# karmanDB_MCU.net
KiCad netlist of a schematic drawn in Altium Designer
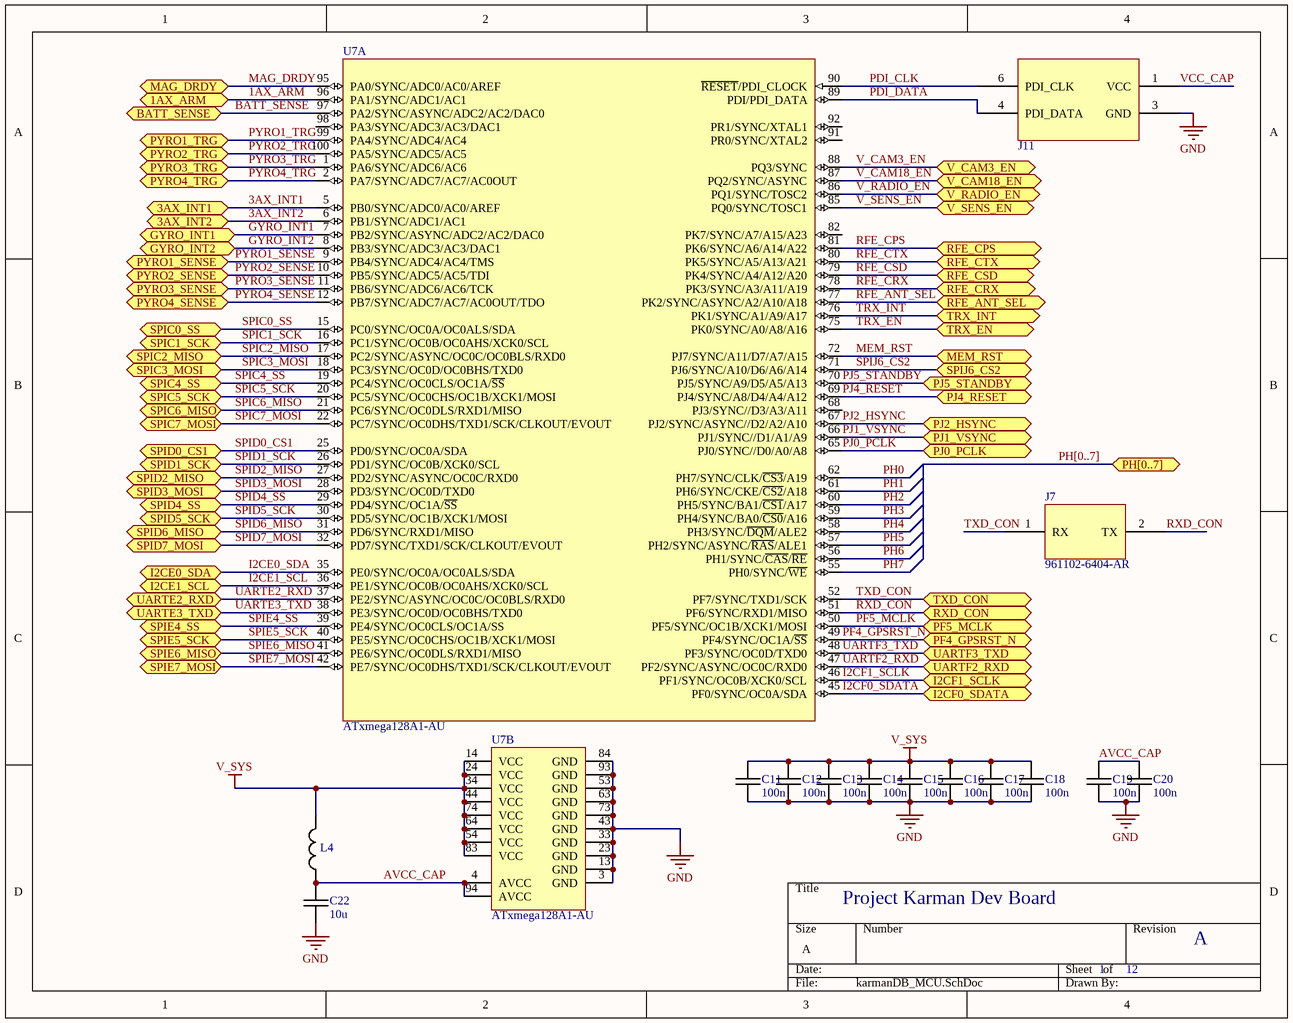
[diagram p0: karmanDB_MCU.SchDoc]

(export (version "E")
  (design (tool "Eeschema 10.0.6"))
  (components
    (comp (ref "C11")
      (value "100n")
      (footprint "MURATA_GRM_0603")
      (description "CAP CER 0.1UF 6.3V 10% X7R 0603")
      (fields
        (field (name "MANUFACTURER") "Murata Electronics North America")
        (field (name "MANUFACTURER PART NUMBER") "GRM188R70J104KA01D")
      )
      (libsource (lib "project_symbols") (part "CAP_MURATA_GRM188R70J104KA01D"))
    )
    (comp (ref "C12")
      (value "100n")
      (footprint "MURATA_GRM_0603")
      (description "CAP CER 0.1UF 6.3V 10% X7R 0603")
      (fields
        (field (name "MANUFACTURER") "Murata Electronics North America")
        (field (name "MANUFACTURER PART NUMBER") "GRM188R70J104KA01D")
      )
      (libsource (lib "project_symbols") (part "CAP_MURATA_GRM188R70J104KA01D"))
    )
    (comp (ref "C13")
      (value "100n")
      (footprint "MURATA_GRM_0603")
      (description "CAP CER 0.1UF 6.3V 10% X7R 0603")
      (fields
        (field (name "MANUFACTURER") "Murata Electronics North America")
        (field (name "MANUFACTURER PART NUMBER") "GRM188R70J104KA01D")
      )
      (libsource (lib "project_symbols") (part "CAP_MURATA_GRM188R70J104KA01D"))
    )
    (comp (ref "C14")
      (value "100n")
      (footprint "MURATA_GRM_0603")
      (description "CAP CER 0.1UF 6.3V 10% X7R 0603")
      (fields
        (field (name "MANUFACTURER") "Murata Electronics North America")
        (field (name "MANUFACTURER PART NUMBER") "GRM188R70J104KA01D")
      )
      (libsource (lib "project_symbols") (part "CAP_MURATA_GRM188R70J104KA01D"))
    )
    (comp (ref "C15")
      (value "100n")
      (footprint "MURATA_GRM_0603")
      (description "CAP CER 0.1UF 6.3V 10% X7R 0603")
      (fields
        (field (name "MANUFACTURER") "Murata Electronics North America")
        (field (name "MANUFACTURER PART NUMBER") "GRM188R70J104KA01D")
      )
      (libsource (lib "project_symbols") (part "CAP_MURATA_GRM188R70J104KA01D"))
    )
    (comp (ref "C16")
      (value "100n")
      (footprint "MURATA_GRM_0603")
      (description "CAP CER 0.1UF 6.3V 10% X7R 0603")
      (fields
        (field (name "MANUFACTURER") "Murata Electronics North America")
        (field (name "MANUFACTURER PART NUMBER") "GRM188R70J104KA01D")
      )
      (libsource (lib "project_symbols") (part "CAP_MURATA_GRM188R70J104KA01D"))
    )
    (comp (ref "C17")
      (value "100n")
      (footprint "MURATA_GRM_0603")
      (description "CAP CER 0.1UF 6.3V 10% X7R 0603")
      (fields
        (field (name "MANUFACTURER") "Murata Electronics North America")
        (field (name "MANUFACTURER PART NUMBER") "GRM188R70J104KA01D")
      )
      (libsource (lib "project_symbols") (part "CAP_MURATA_GRM188R70J104KA01D"))
    )
    (comp (ref "C18")
      (value "100n")
      (footprint "MURATA_GRM_0603")
      (description "CAP CER 0.1UF 6.3V 10% X7R 0603")
      (fields
        (field (name "MANUFACTURER") "Murata Electronics North America")
        (field (name "MANUFACTURER PART NUMBER") "GRM188R70J104KA01D")
      )
      (libsource (lib "project_symbols") (part "CAP_MURATA_GRM188R70J104KA01D"))
    )
    (comp (ref "C19")
      (value "100n")
      (footprint "MURATA_GRM_0603")
      (description "CAP CER 0.1UF 6.3V 10% X7R 0603")
      (fields
        (field (name "MANUFACTURER") "Murata Electronics North America")
        (field (name "MANUFACTURER PART NUMBER") "GRM188R70J104KA01D")
      )
      (libsource (lib "project_symbols") (part "CAP_MURATA_GRM188R70J104KA01D"))
    )
    (comp (ref "C20")
      (value "100n")
      (footprint "MURATA_GRM_0603")
      (description "CAP CER 0.1UF 6.3V 10% X7R 0603")
      (fields
        (field (name "MANUFACTURER") "Murata Electronics North America")
        (field (name "MANUFACTURER PART NUMBER") "GRM188R70J104KA01D")
      )
      (libsource (lib "project_symbols") (part "CAP_MURATA_GRM188R70J104KA01D"))
    )
    (comp (ref "C22")
      (value "10u")
      (footprint "MURATA_GRM_0603")
      (description "CAP CER 10UF 6.3V 20% X5R 0603")
      (fields
        (field (name "MANUFACTURER") "Murata Electronics North America")
        (field (name "MANUFACTURER PART NUMBER") "GRM188R60J106ME47J")
      )
      (libsource (lib "project_symbols") (part "CAP_MURATA_GRM188R60J106"))
    )
    (comp (ref "J7")
      (value "961102-6404-AR")
      (footprint "3M_961102-6X04")
      (description "CONN HEADER VERT SGL 2POS GOLD")
      (fields (field (name "MANUFACTURER") "3M"))
      (libsource (lib "karman_pcb") (part "961102-6404-AR"))
    )
    (comp (ref "J11")
      (value "961206-6404-AR")
      (footprint "961206-6404-AR")
      (description "CONN HEADER VERT DUAL 6POS GOLD")
      (fields (field (name "MANUFACTURER") "3M"))
      (libsource (lib "karman_pcb") (part "961206-6404-AR"))
    )
    (comp (ref "L4")
      (value "BLM15BB221SN1D")
      (footprint "BLM15")
      (description "FERRITE CHIP 220 OHM 200MA 0402")
      (fields (field (name "MANUFACTURER") "Murata Electronics North America"))
      (libsource (lib "karman_pcb") (part "BLM15BB221SN1D"))
    )
    (comp (ref "U7")
      (value "ATxmega128A1-AU")
      (footprint "100A_N")
      (fields (field (name "PUBLISHER") "Altium Limited"))
      (libsource (lib "Atmel Microcontroller 8-16-Bit AVR XMEGA") (part "ATxmega128A1-AU"))
    )
  )
  (nets
    (net (code "1") (name "/1AX_ARM") (class "Default")
      (node (ref "U7") (pin "96") (pinfunction "PA1/SYNC/ADC1/AC1_96") (pintype "bidirectional"))
    )
    (net (code "2") (name "/3AX_INT1") (class "Default")
      (node (ref "U7") (pin "5") (pinfunction "PB0/SYNC/ADC0/AC0/AREF_5") (pintype "bidirectional"))
    )
    (net (code "3") (name "/3AX_INT2") (class "Default")
      (node (ref "U7") (pin "6") (pinfunction "PB1/SYNC/ADC1/AC1_6") (pintype "bidirectional"))
    )
    (net (code "4") (name "/AVCC_CAP") (class "Default")
      (node (ref "C19") (pin "1") (pintype "passive"))
      (node (ref "C20") (pin "1") (pintype "passive"))
      (node (ref "C22") (pin "1") (pintype "passive"))
      (node (ref "L4") (pin "1") (pinfunction "1_1") (pintype "passive"))
      (node (ref "U7") (pin "4") (pinfunction "AVCC_4") (pintype "power_in"))
      (node (ref "U7") (pin "94") (pinfunction "AVCC_94") (pintype "power_in"))
    )
    (net (code "5") (name "/BATT_SENSE") (class "Default")
      (node (ref "U7") (pin "97") (pinfunction "PA2/SYNC/ASYNC/ADC2/AC2/DAC0_97") (pintype "bidirectional"))
    )
    (net (code "6") (name "/GYRO_INT1") (class "Default")
      (node (ref "U7") (pin "7") (pinfunction "PB2/SYNC/ASYNC/ADC2/AC2/DAC0_7") (pintype "bidirectional"))
    )
    (net (code "7") (name "/GYRO_INT2") (class "Default")
      (node (ref "U7") (pin "8") (pinfunction "PB3/SYNC/ADC3/AC3/DAC1_8") (pintype "bidirectional"))
    )
    (net (code "8") (name "/I2CE0_SDA") (class "Default")
      (node (ref "U7") (pin "35") (pinfunction "PE0/SYNC/OC0A/OC0ALS/SDA_35") (pintype "bidirectional"))
    )
    (net (code "9") (name "/I2CE1_SCL") (class "Default")
      (node (ref "U7") (pin "36") (pinfunction "PE1/SYNC/OC0B/OC0AHS/XCK0/SCL_36") (pintype "bidirectional"))
    )
    (net (code "10") (name "/I2CF0_SDATA") (class "Default")
      (node (ref "U7") (pin "45") (pinfunction "PF0/SYNC/OC0A/SDA_45") (pintype "bidirectional"))
    )
    (net (code "11") (name "/I2CF1_SCLK") (class "Default")
      (node (ref "U7") (pin "46") (pinfunction "PF1/SYNC/OC0B/XCK0/SCL_46") (pintype "bidirectional"))
    )
    (net (code "12") (name "/MAG_DRDY") (class "Default")
      (node (ref "U7") (pin "95") (pinfunction "PA0/SYNC/ADC0/AC0/AREF_95") (pintype "bidirectional"))
    )
    (net (code "13") (name "/MEM_RST") (class "Default")
      (node (ref "U7") (pin "72") (pinfunction "PJ7/SYNC/A11/D7/A7/A15_72") (pintype "bidirectional"))
    )
    (net (code "14") (name "/PDI_CLK") (class "Default")
      (node (ref "J11") (pin "6") (pinfunction "PDI_CLK_6") (pintype "passive"))
      (node (ref "U7") (pin "90") (pinfunction "~{RESET}/PDI_CLOCK_90") (pintype "input"))
    )
    (net (code "15") (name "/PDI_DATA") (class "Default")
      (node (ref "J11") (pin "4") (pinfunction "PDI_DATA_4") (pintype "passive"))
      (node (ref "U7") (pin "89") (pinfunction "PDI/PDI_DATA_89") (pintype "bidirectional"))
    )
    (net (code "16") (name "/PF4_GPSRST_N") (class "Default")
      (node (ref "U7") (pin "49") (pinfunction "PF4/SYNC/OC1A/~{SS}_49") (pintype "bidirectional"))
    )
    (net (code "17") (name "/PF5_MCLK") (class "Default")
      (node (ref "U7") (pin "50") (pinfunction "PF5/SYNC/OC1B/XCK1/MOSI_50") (pintype "bidirectional"))
    )
    (net (code "18") (name "/PH0") (class "Default")
      (node (ref "U7") (pin "62") (pinfunction "PH7/SYNC/CLK/~{CS3}/A19_62") (pintype "bidirectional"))
    )
    (net (code "19") (name "/PH1") (class "Default")
      (node (ref "U7") (pin "61") (pinfunction "PH6/SYNC/CKE/~{CS2}/A18_61") (pintype "bidirectional"))
    )
    (net (code "20") (name "/PH2") (class "Default")
      (node (ref "U7") (pin "60") (pinfunction "PH5/SYNC/BA1/~{CS1}/A17_60") (pintype "bidirectional"))
    )
    (net (code "21") (name "/PH3") (class "Default")
      (node (ref "U7") (pin "59") (pinfunction "PH4/SYNC/BA0/~{CS0}/A16_59") (pintype "bidirectional"))
    )
    (net (code "22") (name "/PH4") (class "Default")
      (node (ref "U7") (pin "58") (pinfunction "PH3/SYNC/~{DQM}/ALE2_58") (pintype "bidirectional"))
    )
    (net (code "23") (name "/PH5") (class "Default")
      (node (ref "U7") (pin "57") (pinfunction "PH2/SYNC/ASYNC/~{RAS}/ALE1_57") (pintype "bidirectional"))
    )
    (net (code "24") (name "/PH6") (class "Default")
      (node (ref "U7") (pin "56") (pinfunction "PH1/SYNC/~{CAS}/~{RE}_56") (pintype "bidirectional"))
    )
    (net (code "25") (name "/PH7") (class "Default")
      (node (ref "U7") (pin "55") (pinfunction "PH0/SYNC/~{WE}_55") (pintype "bidirectional"))
    )
    (net (code "27") (name "/PJ0_PCLK") (class "Default")
      (node (ref "U7") (pin "65") (pinfunction "PJ0/SYNC//D0/A0/A8_65") (pintype "bidirectional"))
    )
    (net (code "28") (name "/PJ1_VSYNC") (class "Default")
      (node (ref "U7") (pin "66") (pinfunction "PJ1/SYNC//D1/A1/A9_66") (pintype "bidirectional"))
    )
    (net (code "29") (name "/PJ2_HSYNC") (class "Default")
      (node (ref "U7") (pin "67") (pinfunction "PJ2/SYNC/ASYNC//D2/A2/A10_67") (pintype "bidirectional"))
    )
    (net (code "30") (name "/PJ4_RESET") (class "Default")
      (node (ref "U7") (pin "69") (pinfunction "PJ4/SYNC/A8/D4/A4/A12_69") (pintype "bidirectional"))
    )
    (net (code "31") (name "/PJ5_STANDBY") (class "Default")
      (node (ref "U7") (pin "70") (pinfunction "PJ5/SYNC/A9/D5/A5/A13_70") (pintype "bidirectional"))
    )
    (net (code "32") (name "/PYRO1_SENSE") (class "Default")
      (node (ref "U7") (pin "9") (pinfunction "PB4/SYNC/ADC4/AC4/TMS_9") (pintype "bidirectional"))
    )
    (net (code "33") (name "/PYRO1_TRG") (class "Default")
      (node (ref "U7") (pin "99") (pinfunction "PA4/SYNC/ADC4/AC4_99") (pintype "bidirectional"))
    )
    (net (code "34") (name "/PYRO2_SENSE") (class "Default")
      (node (ref "U7") (pin "10") (pinfunction "PB5/SYNC/ADC5/AC5/TDI_10") (pintype "bidirectional"))
    )
    (net (code "35") (name "/PYRO2_TRG") (class "Default")
      (node (ref "U7") (pin "100") (pinfunction "PA5/SYNC/ADC5/AC5_100") (pintype "bidirectional"))
    )
    (net (code "36") (name "/PYRO3_SENSE") (class "Default")
      (node (ref "U7") (pin "11") (pinfunction "PB6/SYNC/ADC6/AC6/TCK_11") (pintype "bidirectional"))
    )
    (net (code "37") (name "/PYRO3_TRG") (class "Default")
      (node (ref "U7") (pin "1") (pinfunction "PA6/SYNC/ADC6/AC6_1") (pintype "bidirectional"))
    )
    (net (code "38") (name "/PYRO4_SENSE") (class "Default")
      (node (ref "U7") (pin "12") (pinfunction "PB7/SYNC/ADC7/AC7/AC0OUT/TDO_12") (pintype "bidirectional"))
    )
    (net (code "39") (name "/PYRO4_TRG") (class "Default")
      (node (ref "U7") (pin "2") (pinfunction "PA7/SYNC/ADC7/AC7/AC0OUT_2") (pintype "bidirectional"))
    )
    (net (code "40") (name "/RFE_ANT_SEL") (class "Default")
      (node (ref "U7") (pin "77") (pinfunction "PK2/SYNC/ASYNC/A2/A10/A18_77") (pintype "bidirectional"))
    )
    (net (code "41") (name "/RFE_CPS") (class "Default")
      (node (ref "U7") (pin "81") (pinfunction "PK6/SYNC/A6/A14/A22_81") (pintype "bidirectional"))
    )
    (net (code "42") (name "/RFE_CRX") (class "Default")
      (node (ref "U7") (pin "78") (pinfunction "PK3/SYNC/A3/A11/A19_78") (pintype "bidirectional"))
    )
    (net (code "43") (name "/RFE_CSD") (class "Default")
      (node (ref "U7") (pin "79") (pinfunction "PK4/SYNC/A4/A12/A20_79") (pintype "bidirectional"))
    )
    (net (code "44") (name "/RFE_CTX") (class "Default")
      (node (ref "U7") (pin "80") (pinfunction "PK5/SYNC/A5/A13/A21_80") (pintype "bidirectional"))
    )
    (net (code "45") (name "/RXD_CON") (class "Default")
      (node (ref "J7") (pin "2") (pinfunction "TX_2") (pintype "passive"))
      (node (ref "U7") (pin "51") (pinfunction "PF6/SYNC/RXD1/MISO_51") (pintype "bidirectional"))
    )
    (net (code "46") (name "/SPIC0_SS") (class "Default")
      (node (ref "U7") (pin "15") (pinfunction "PC0/SYNC/OC0A/OC0ALS/SDA_15") (pintype "bidirectional"))
    )
    (net (code "47") (name "/SPIC1_SCK") (class "Default")
      (node (ref "U7") (pin "16") (pinfunction "PC1/SYNC/OC0B/OC0AHS/XCK0/SCL_16") (pintype "bidirectional"))
    )
    (net (code "48") (name "/SPIC2_MISO") (class "Default")
      (node (ref "U7") (pin "17") (pinfunction "PC2/SYNC/ASYNC/OC0C/OC0BLS/RXD0_17") (pintype "bidirectional"))
    )
    (net (code "49") (name "/SPIC3_MOSI") (class "Default")
      (node (ref "U7") (pin "18") (pinfunction "PC3/SYNC/OC0D/OC0BHS/TXD0_18") (pintype "bidirectional"))
    )
    (net (code "50") (name "/SPIC4_SS") (class "Default")
      (node (ref "U7") (pin "19") (pinfunction "PC4/SYNC/OC0CLS/OC1A/~{SS}_19") (pintype "bidirectional"))
    )
    (net (code "51") (name "/SPIC5_SCK") (class "Default")
      (node (ref "U7") (pin "20") (pinfunction "PC5/SYNC/OC0CHS/OC1B/XCK1/MOSI_20") (pintype "bidirectional"))
    )
    (net (code "52") (name "/SPIC6_MISO") (class "Default")
      (node (ref "U7") (pin "21") (pinfunction "PC6/SYNC/OC0DLS/RXD1/MISO_21") (pintype "bidirectional"))
    )
    (net (code "53") (name "/SPIC7_MOSI") (class "Default")
      (node (ref "U7") (pin "22") (pinfunction "PC7/SYNC/OC0DHS/TXD1/SCK/CLKOUT/EVOUT_22") (pintype "bidirectional"))
    )
    (net (code "54") (name "/SPID0_CS1") (class "Default")
      (node (ref "U7") (pin "25") (pinfunction "PD0/SYNC/OC0A/SDA_25") (pintype "bidirectional"))
    )
    (net (code "55") (name "/SPID1_SCK") (class "Default")
      (node (ref "U7") (pin "26") (pinfunction "PD1/SYNC/OC0B/XCK0/SCL_26") (pintype "bidirectional"))
    )
    (net (code "56") (name "/SPID2_MISO") (class "Default")
      (node (ref "U7") (pin "27") (pinfunction "PD2/SYNC/ASYNC/OC0C/RXD0_27") (pintype "bidirectional"))
    )
    (net (code "57") (name "/SPID3_MOSI") (class "Default")
      (node (ref "U7") (pin "28") (pinfunction "PD3/SYNC/OC0D/TXD0_28") (pintype "bidirectional"))
    )
    (net (code "58") (name "/SPID4_SS") (class "Default")
      (node (ref "U7") (pin "29") (pinfunction "PD4/SYNC/OC1A/~{SS}_29") (pintype "bidirectional"))
    )
    (net (code "59") (name "/SPID5_SCK") (class "Default")
      (node (ref "U7") (pin "30") (pinfunction "PD5/SYNC/OC1B/XCK1/MOSI_30") (pintype "bidirectional"))
    )
    (net (code "60") (name "/SPID6_MISO") (class "Default")
      (node (ref "U7") (pin "31") (pinfunction "PD6/SYNC/RXD1/MISO_31") (pintype "bidirectional"))
    )
    (net (code "61") (name "/SPID7_MOSI") (class "Default")
      (node (ref "U7") (pin "32") (pinfunction "PD7/SYNC/TXD1/SCK/CLKOUT/EVOUT_32") (pintype "bidirectional"))
    )
    (net (code "62") (name "/SPIE4_SS") (class "Default")
      (node (ref "U7") (pin "39") (pinfunction "PE4/SYNC/OC0CLS/OC1A/SS_39") (pintype "bidirectional"))
    )
    (net (code "63") (name "/SPIE5_SCK") (class "Default")
      (node (ref "U7") (pin "40") (pinfunction "PE5/SYNC/OC0CHS/OC1B/XCK1/MOSI_40") (pintype "bidirectional"))
    )
    (net (code "64") (name "/SPIE6_MISO") (class "Default")
      (node (ref "U7") (pin "41") (pinfunction "PE6/SYNC/OC0DLS/RXD1/MISO_41") (pintype "bidirectional"))
    )
    (net (code "65") (name "/SPIE7_MOSI") (class "Default")
      (node (ref "U7") (pin "42") (pinfunction "PE7/SYNC/OC0DHS/TXD1/SCK/CLKOUT/EVOUT_42") (pintype "bidirectional"))
    )
    (net (code "66") (name "/SPIJ6_CS2") (class "Default")
      (node (ref "U7") (pin "71") (pinfunction "PJ6/SYNC/A10/D6/A6/A14_71") (pintype "bidirectional"))
    )
    (net (code "67") (name "/TRX_EN") (class "Default")
      (node (ref "U7") (pin "75") (pinfunction "PK0/SYNC/A0/A8/A16_75") (pintype "bidirectional"))
    )
    (net (code "68") (name "/TRX_INT") (class "Default")
      (node (ref "U7") (pin "76") (pinfunction "PK1/SYNC/A1/A9/A17_76") (pintype "bidirectional"))
    )
    (net (code "69") (name "/TXD_CON") (class "Default")
      (node (ref "J7") (pin "1") (pinfunction "RX_1") (pintype "passive"))
      (node (ref "U7") (pin "52") (pinfunction "PF7/SYNC/TXD1/SCK_52") (pintype "bidirectional"))
    )
    (net (code "70") (name "/UARTE2_RXD") (class "Default")
      (node (ref "U7") (pin "37") (pinfunction "PE2/SYNC/ASYNC/OC0C/OC0BLS/RXD0_37") (pintype "bidirectional"))
    )
    (net (code "71") (name "/UARTE3_TXD") (class "Default")
      (node (ref "U7") (pin "38") (pinfunction "PE3/SYNC/OC0D/OC0BHS/TXD0_38") (pintype "bidirectional"))
    )
    (net (code "72") (name "/UARTF2_RXD") (class "Default")
      (node (ref "U7") (pin "47") (pinfunction "PF2/SYNC/ASYNC/OC0C/RXD0_47") (pintype "bidirectional"))
    )
    (net (code "73") (name "/UARTF3_TXD") (class "Default")
      (node (ref "U7") (pin "48") (pinfunction "PF3/SYNC/OC0D/TXD0_48") (pintype "bidirectional"))
    )
    (net (code "74") (name "/VCC_CAP") (class "Default")
      (node (ref "J11") (pin "1") (pinfunction "VCC_1") (pintype "passive"))
    )
    (net (code "75") (name "/V_CAM3_EN") (class "Default")
      (node (ref "U7") (pin "88") (pinfunction "PQ3/SYNC_88") (pintype "bidirectional"))
    )
    (net (code "76") (name "/V_CAM18_EN") (class "Default")
      (node (ref "U7") (pin "87") (pinfunction "PQ2/SYNC/ASYNC_87") (pintype "bidirectional"))
    )
    (net (code "77") (name "/V_RADIO_EN") (class "Default")
      (node (ref "U7") (pin "86") (pinfunction "PQ1/SYNC/TOSC2_86") (pintype "bidirectional"))
    )
    (net (code "78") (name "/V_SENS_EN") (class "Default")
      (node (ref "U7") (pin "85") (pinfunction "PQ0/SYNC/TOSC1_85") (pintype "bidirectional"))
    )
    (net (code "79") (name "GND") (class "Default")
      (node (ref "C11") (pin "2") (pintype "passive"))
      (node (ref "C12") (pin "2") (pintype "passive"))
      (node (ref "C13") (pin "2") (pintype "passive"))
      (node (ref "C14") (pin "2") (pintype "passive"))
      (node (ref "C15") (pin "2") (pintype "passive"))
      (node (ref "C16") (pin "2") (pintype "passive"))
      (node (ref "C17") (pin "2") (pintype "passive"))
      (node (ref "C18") (pin "2") (pintype "passive"))
      (node (ref "C19") (pin "2") (pintype "passive"))
      (node (ref "C20") (pin "2") (pintype "passive"))
      (node (ref "C22") (pin "2") (pintype "passive"))
      (node (ref "J11") (pin "3") (pinfunction "GND_3") (pintype "passive"))
      (node (ref "U7") (pin "13") (pinfunction "GND_13") (pintype "power_in"))
      (node (ref "U7") (pin "23") (pinfunction "GND_23") (pintype "power_in"))
      (node (ref "U7") (pin "3") (pinfunction "GND_3") (pintype "power_in"))
      (node (ref "U7") (pin "33") (pinfunction "GND_33") (pintype "power_in"))
      (node (ref "U7") (pin "43") (pinfunction "GND_43") (pintype "power_in"))
      (node (ref "U7") (pin "53") (pinfunction "GND_53") (pintype "power_in"))
      (node (ref "U7") (pin "63") (pinfunction "GND_63") (pintype "power_in"))
      (node (ref "U7") (pin "73") (pinfunction "GND_73") (pintype "power_in"))
      (node (ref "U7") (pin "84") (pinfunction "GND_84") (pintype "power_in"))
      (node (ref "U7") (pin "93") (pinfunction "GND_93") (pintype "power_in"))
    )
    (net (code "80") (name "V_SYS") (class "Default")
      (node (ref "C11") (pin "1") (pintype "passive"))
      (node (ref "C12") (pin "1") (pintype "passive"))
      (node (ref "C13") (pin "1") (pintype "passive"))
      (node (ref "C14") (pin "1") (pintype "passive"))
      (node (ref "C15") (pin "1") (pintype "passive"))
      (node (ref "C16") (pin "1") (pintype "passive"))
      (node (ref "C17") (pin "1") (pintype "passive"))
      (node (ref "C18") (pin "1") (pintype "passive"))
      (node (ref "L4") (pin "2") (pinfunction "2_2") (pintype "passive"))
      (node (ref "U7") (pin "14") (pinfunction "VCC_14") (pintype "power_in"))
      (node (ref "U7") (pin "24") (pinfunction "VCC_24") (pintype "power_in"))
      (node (ref "U7") (pin "34") (pinfunction "VCC_34") (pintype "power_in"))
      (node (ref "U7") (pin "44") (pinfunction "VCC_44") (pintype "power_in"))
      (node (ref "U7") (pin "54") (pinfunction "VCC_54") (pintype "power_in"))
      (node (ref "U7") (pin "64") (pinfunction "VCC_64") (pintype "power_in"))
      (node (ref "U7") (pin "74") (pinfunction "VCC_74") (pintype "power_in"))
      (node (ref "U7") (pin "83") (pinfunction "VCC_83") (pintype "power_in"))
    )
    (net (code "81") (name "unconnected-(U7A-PA3{slash}SYNC{slash}ADC3{slash}AC3{slash}DAC1-Pad98)") (class "Default")
      (node (ref "U7") (pin "98") (pinfunction "PA3/SYNC/ADC3/AC3/DAC1_98") (pintype "bidirectional"))
    )
    (net (code "82") (name "unconnected-(U7A-PJ3{slash}SYNC{slash}{slash}D3{slash}A3{slash}A11-Pad68)") (class "Default")
      (node (ref "U7") (pin "68") (pinfunction "PJ3/SYNC//D3/A3/A11_68") (pintype "bidirectional"))
    )
    (net (code "83") (name "unconnected-(U7A-PK7{slash}SYNC{slash}A7{slash}A15{slash}A23-Pad82)") (class "Default")
      (node (ref "U7") (pin "82") (pinfunction "PK7/SYNC/A7/A15/A23_82") (pintype "bidirectional"))
    )
    (net (code "84") (name "unconnected-(U7A-PR0{slash}SYNC{slash}XTAL2-Pad91)") (class "Default")
      (node (ref "U7") (pin "91") (pinfunction "PR0/SYNC/XTAL2_91") (pintype "bidirectional"))
    )
    (net (code "85") (name "unconnected-(U7A-PR1{slash}SYNC{slash}XTAL1-Pad92)") (class "Default")
      (node (ref "U7") (pin "92") (pinfunction "PR1/SYNC/XTAL1_92") (pintype "bidirectional"))
    )
  )
)
